# FidoBark11.net
KiCad netlist of a schematic drawn in EAGLE
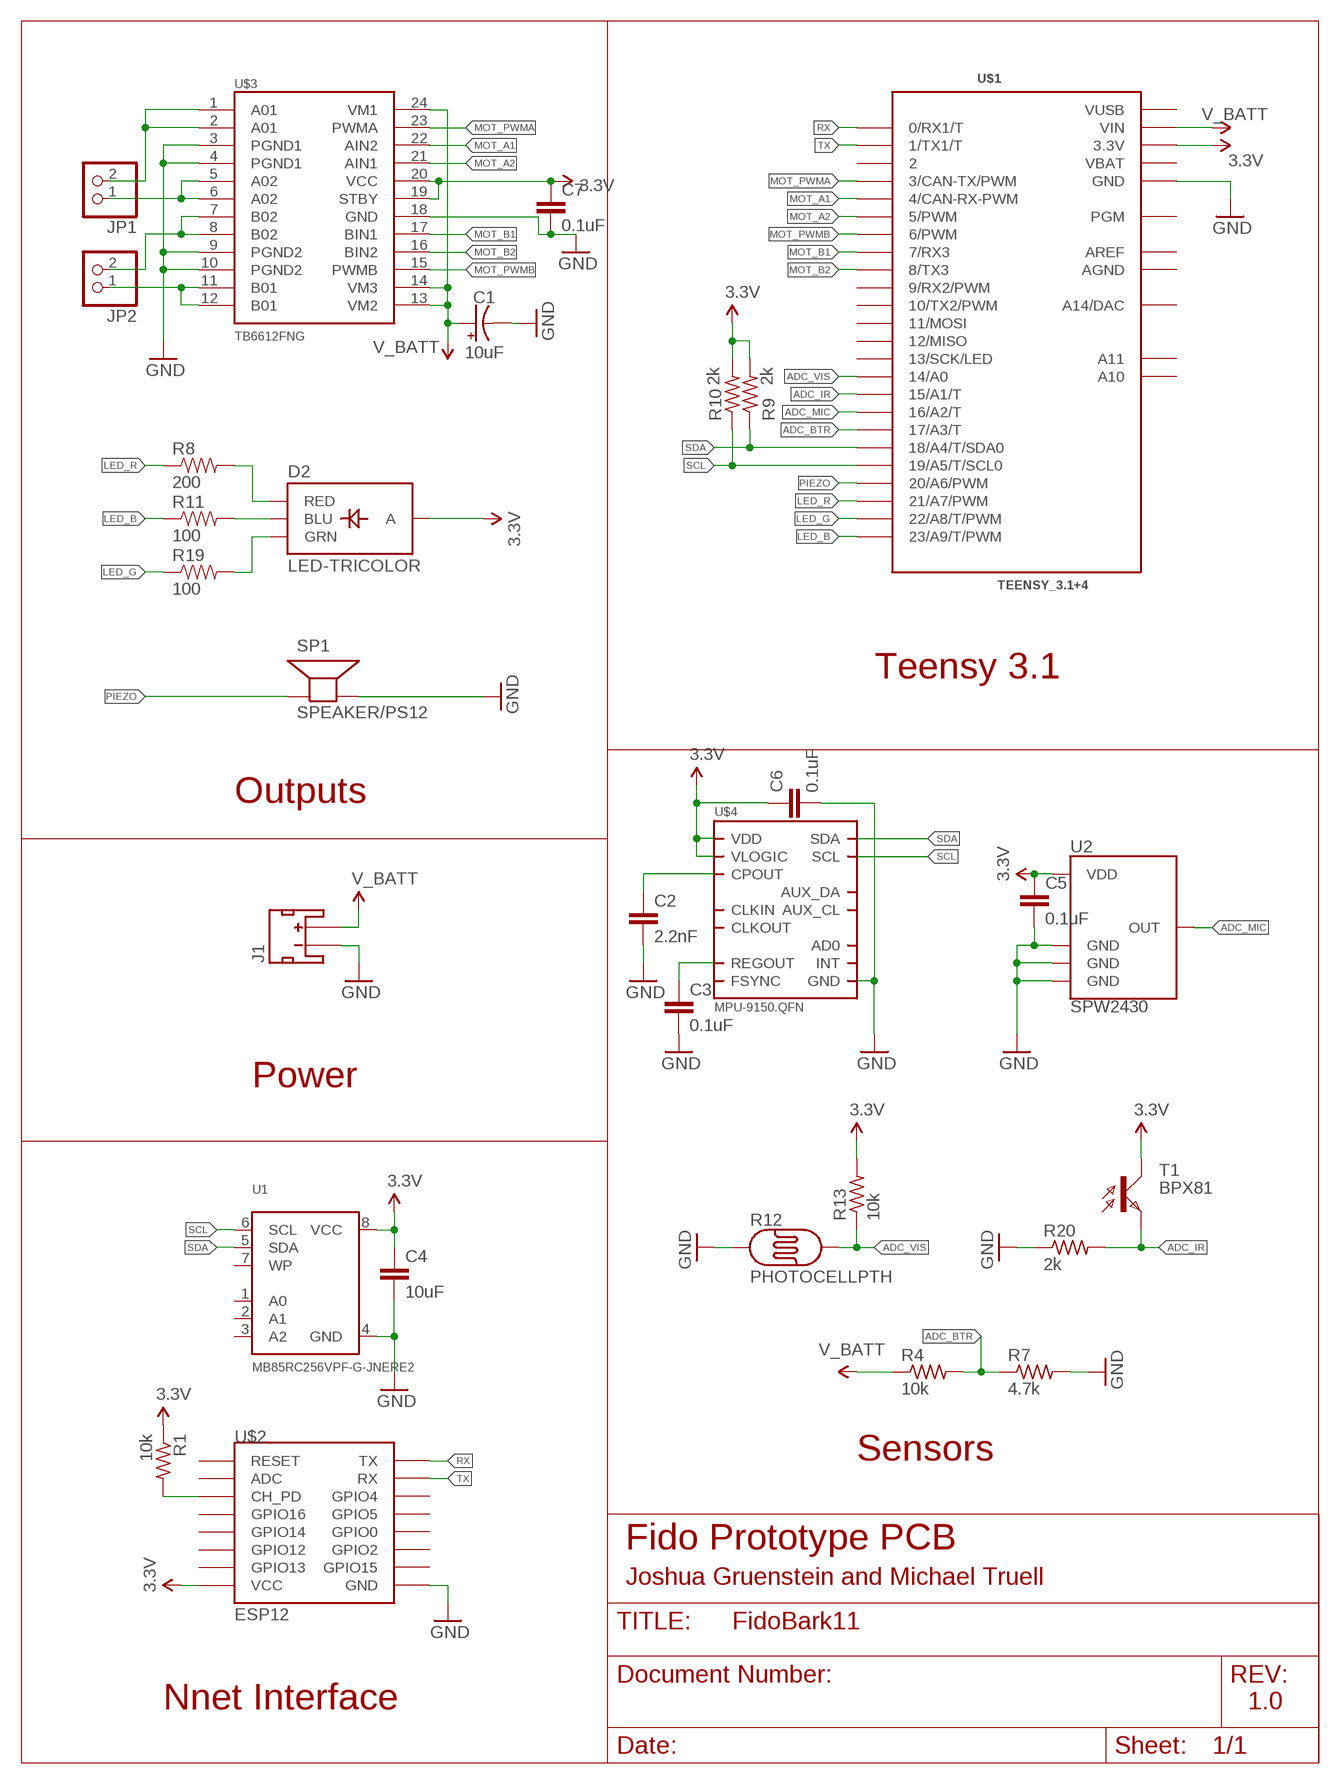
[diagram p0: schematic, sheet 1]

(export (version "E")
  (design (tool "Eeschema 10.0.6"))
  (components
    (comp (ref "C1")
      (value "10uF")
      (footprint "eagle-import:EIA3216")
      (libsource (lib "eagle-import") (part "CAP_POL1206"))
    )
    (comp (ref "C2")
      (value "2.2nF")
      (footprint "eagle-import:C0603")
      (libsource (lib "eagle-import") (part "C-EUC0603"))
    )
    (comp (ref "C3")
      (value "0.1uF")
      (footprint "eagle-import:C0603")
      (libsource (lib "eagle-import") (part "C-EUC0603"))
    )
    (comp (ref "C4")
      (value "10uF")
      (footprint "eagle-import:0603-CAP")
      (libsource (lib "eagle-import") (part "CAP0603-CAP"))
    )
    (comp (ref "C5")
      (value "0.1uF")
      (footprint "eagle-import:C0603")
      (libsource (lib "eagle-import") (part "resistor_C-EUC0603"))
    )
    (comp (ref "C6")
      (value "0.1uF")
      (footprint "eagle-import:C0603")
      (libsource (lib "eagle-import") (part "resistor_C-EUC0603"))
    )
    (comp (ref "C7")
      (value "0.1uF")
      (footprint "eagle-import:C0603")
      (libsource (lib "eagle-import") (part "resistor_C-EUC0603"))
    )
    (comp (ref "D2")
      (value "LED-TRICOLOR")
      (footprint "eagle-import:LED-TRICOLOR-SMD")
      (libsource (lib "eagle-import") (part "LED-TRICOLOR"))
    )
    (comp (ref "J1")
      (value "JST_2MM_MALE")
      (footprint "eagle-import:JST-2-SMD")
      (libsource (lib "eagle-import") (part "JST_2MM_MALE"))
    )
    (comp (ref "JP1")
      (value "PINHD-1X2")
      (footprint "eagle-import:1X02")
      (libsource (lib "eagle-import") (part "PINHD-1X2"))
    )
    (comp (ref "JP2")
      (value "PINHD-1X2")
      (footprint "eagle-import:1X02")
      (libsource (lib "eagle-import") (part "PINHD-1X2"))
    )
    (comp (ref "R1")
      (value "10k")
      (footprint "eagle-import:R0603")
      (libsource (lib "eagle-import") (part "rcl_R-US_R0603"))
    )
    (comp (ref "R4")
      (value "10k")
      (footprint "eagle-import:R0603")
      (libsource (lib "eagle-import") (part "rcl_R-US_R0603"))
    )
    (comp (ref "R7")
      (value "4.7k")
      (footprint "eagle-import:R0603")
      (libsource (lib "eagle-import") (part "rcl_R-US_R0603"))
    )
    (comp (ref "R8")
      (value "200")
      (footprint "eagle-import:0402-RES")
      (libsource (lib "eagle-import") (part "RESISTOR0402-RES"))
    )
    (comp (ref "R9")
      (value "2k")
      (footprint "eagle-import:R0603")
      (libsource (lib "eagle-import") (part "rcl_R-US_R0603"))
    )
    (comp (ref "R10")
      (value "2k")
      (footprint "eagle-import:R0603")
      (libsource (lib "eagle-import") (part "rcl_R-US_R0603"))
    )
    (comp (ref "R11")
      (value "100")
      (footprint "eagle-import:0402-RES")
      (libsource (lib "eagle-import") (part "RESISTOR0402-RES"))
    )
    (comp (ref "R12")
      (value "PHOTOCELLPTH")
      (footprint "eagle-import:PHOTOCELL")
      (libsource (lib "eagle-import") (part "PHOTOCELLPTH"))
    )
    (comp (ref "R13")
      (value "10k")
      (footprint "eagle-import:R0603")
      (libsource (lib "eagle-import") (part "R-US_R0603"))
    )
    (comp (ref "R19")
      (value "100")
      (footprint "eagle-import:0402-RES")
      (libsource (lib "eagle-import") (part "RESISTOR0402-RES"))
    )
    (comp (ref "R20")
      (value "2k")
      (footprint "eagle-import:R0603")
      (libsource (lib "eagle-import") (part "R-US_R0603"))
    )
    (comp (ref "SP1")
      (value "SPEAKER/PS12")
      (footprint "eagle-import:PS12")
      (libsource (lib "eagle-import") (part "SPEAKER/PS12"))
    )
    (comp (ref "T1")
      (value "BPX81")
      (footprint "eagle-import:BPX81")
      (libsource (lib "eagle-import") (part "BPX81"))
    )
    (comp (ref "U$1")
      (value "TEENSY_3.1+4")
      (footprint "eagle-import:TEENSY_3.1+4")
      (libsource (lib "eagle-import") (part "TEENSY_3.1+4"))
    )
    (comp (ref "U$2")
      (value "ESP12")
      (footprint "eagle-import:ESP12")
      (libsource (lib "eagle-import") (part "ESP12"))
    )
    (comp (ref "U$3")
      (value "TB6612FNG")
      (footprint "eagle-import:SSOP24")
      (libsource (lib "eagle-import") (part "TB6612FNG"))
    )
    (comp (ref "U$4")
      (value "MPU-9150.QFN")
      (footprint "eagle-import:QFN.24.4X4")
      (libsource (lib "eagle-import") (part "MPU-9150.QFN"))
    )
    (comp (ref "U1")
      (value "MB85RC256VPF-G-JNERE2")
      (footprint "eagle-import:SOIC8_208MIL")
      (libsource (lib "eagle-import") (part "FRAM_SOIC8_I2C"))
    )
    (comp (ref "U2")
      (value "SPW2430")
      (footprint "eagle-import:ADMP401")
      (libsource (lib "eagle-import") (part "ADMP401"))
    )
  )
  (nets
    (net (code "1") (name "/AGND") (class "Default")
      (node (ref "U$1") (pin "AGND") (pinfunction "AGND_AGND") (pintype "power_in"))
    )
    (net (code "2") (name "/AREF") (class "Default")
      (node (ref "U$1") (pin "AREF") (pinfunction "AREF_AREF") (pintype "power_in"))
    )
    (net (code "3") (name "/VBAT") (class "Default")
      (node (ref "U$1") (pin "VBAT") (pinfunction "VBAT_VBAT") (pintype "power_in"))
    )
    (net (code "4") (name "/VUSB") (class "Default")
      (node (ref "U$1") (pin "VUSB") (pinfunction "VUSB_VUSB") (pintype "power_in"))
    )
    (net (code "5") (name "3.3V") (class "Default")
      (node (ref "C4") (pin "1") (pinfunction "1_1") (pintype "passive"))
      (node (ref "C5") (pin "1") (pinfunction "1_1") (pintype "passive"))
      (node (ref "C6") (pin "1") (pinfunction "1_1") (pintype "passive"))
      (node (ref "C7") (pin "1") (pinfunction "1_1") (pintype "passive"))
      (node (ref "D2") (pin "A") (pinfunction "A_A") (pintype "bidirectional"))
      (node (ref "R1") (pin "1") (pinfunction "1_1") (pintype "passive"))
      (node (ref "R10") (pin "2") (pinfunction "2_2") (pintype "passive"))
      (node (ref "R13") (pin "2") (pinfunction "2_2") (pintype "passive"))
      (node (ref "R9") (pin "2") (pinfunction "2_2") (pintype "passive"))
      (node (ref "T1") (pin "C") (pinfunction "C_C") (pintype "passive"))
      (node (ref "U$1") (pin "3.3V") (pinfunction "3.3V_3.3V") (pintype "power_in"))
      (node (ref "U$1") (pin "3.3V1") (pinfunction "3.3V_3.3V1") (pintype "power_in"))
      (node (ref "U$2") (pin "VCC") (pinfunction "VCC_VCC") (pintype "bidirectional"))
      (node (ref "U$3") (pin "19") (pinfunction "STBY_19") (pintype "bidirectional"))
      (node (ref "U$3") (pin "20") (pinfunction "VCC_20") (pintype "bidirectional"))
      (node (ref "U$4") (pin "13") (pinfunction "VDD_13") (pintype "bidirectional"))
      (node (ref "U$4") (pin "3") (pinfunction "VDD_3") (pintype "bidirectional"))
      (node (ref "U$4") (pin "8") (pinfunction "VLOGIC_8") (pintype "bidirectional"))
      (node (ref "U1") (pin "8") (pinfunction "VCC_8") (pintype "power_in"))
      (node (ref "U2") (pin "5") (pinfunction "VDD_5") (pintype "bidirectional"))
    )
    (net (code "6") (name "ADC_BTR") (class "Default")
      (node (ref "R4") (pin "2") (pinfunction "2_2") (pintype "passive"))
      (node (ref "R7") (pin "1") (pinfunction "1_1") (pintype "passive"))
      (node (ref "U$1") (pin "17/A3") (pinfunction "17/A3/T_17/A3") (pintype "bidirectional"))
    )
    (net (code "7") (name "ADC_IR") (class "Default")
      (node (ref "R20") (pin "2") (pinfunction "2_2") (pintype "passive"))
      (node (ref "T1") (pin "E") (pinfunction "E_E") (pintype "passive"))
      (node (ref "U$1") (pin "15/A1") (pinfunction "15/A1/T_15/A1") (pintype "bidirectional"))
    )
    (net (code "8") (name "ADC_MIC") (class "Default")
      (node (ref "U$1") (pin "16/A2") (pinfunction "16/A2/T_16/A2") (pintype "bidirectional"))
      (node (ref "U2") (pin "1") (pinfunction "OUT_1") (pintype "bidirectional"))
    )
    (net (code "9") (name "ADC_VIS") (class "Default")
      (node (ref "R12") (pin "2") (pinfunction "P$2_2") (pintype "bidirectional"))
      (node (ref "R13") (pin "1") (pinfunction "1_1") (pintype "passive"))
      (node (ref "U$1") (pin "14/A0") (pinfunction "14/A0_14/A0") (pintype "bidirectional"))
    )
    (net (code "10") (name "GND") (class "Default")
      (node (ref "C1") (pin "C") (pinfunction "-_C") (pintype "passive"))
      (node (ref "C2") (pin "2") (pinfunction "2_2") (pintype "passive"))
      (node (ref "C3") (pin "2") (pinfunction "2_2") (pintype "passive"))
      (node (ref "C4") (pin "2") (pinfunction "2_2") (pintype "passive"))
      (node (ref "C5") (pin "2") (pinfunction "2_2") (pintype "passive"))
      (node (ref "C6") (pin "2") (pinfunction "2_2") (pintype "passive"))
      (node (ref "C7") (pin "2") (pinfunction "2_2") (pintype "passive"))
      (node (ref "J1") (pin "1") (pinfunction "-_1") (pintype "bidirectional"))
      (node (ref "R12") (pin "1") (pinfunction "P$1_1") (pintype "bidirectional"))
      (node (ref "R20") (pin "1") (pinfunction "1_1") (pintype "passive"))
      (node (ref "R7") (pin "2") (pinfunction "2_2") (pintype "passive"))
      (node (ref "SP1") (pin "P$2") (pinfunction "-_P$2") (pintype "passive"))
      (node (ref "U$1") (pin "GND") (pinfunction "GND_GND") (pintype "power_in"))
      (node (ref "U$1") (pin "GND1") (pinfunction "GND_GND1") (pintype "power_in"))
      (node (ref "U$2") (pin "GND") (pinfunction "GND_GND") (pintype "bidirectional"))
      (node (ref "U$3") (pin "10") (pinfunction "PGND2_10") (pintype "bidirectional"))
      (node (ref "U$3") (pin "18") (pinfunction "GND_18") (pintype "bidirectional"))
      (node (ref "U$3") (pin "3") (pinfunction "PGND1_3") (pintype "bidirectional"))
      (node (ref "U$3") (pin "4") (pinfunction "PGND1_4") (pintype "bidirectional"))
      (node (ref "U$3") (pin "9") (pinfunction "PGND2_9") (pintype "bidirectional"))
      (node (ref "U$4") (pin "15") (pinfunction "GND_15") (pintype "bidirectional"))
      (node (ref "U$4") (pin "17") (pinfunction "GND_17") (pintype "bidirectional"))
      (node (ref "U$4") (pin "18") (pinfunction "GND_18") (pintype "bidirectional"))
      (node (ref "U1") (pin "4") (pinfunction "GND_4") (pintype "power_in"))
      (node (ref "U2") (pin "2") (pinfunction "GND_2") (pintype "bidirectional"))
      (node (ref "U2") (pin "4") (pinfunction "GND_4") (pintype "bidirectional"))
      (node (ref "U2") (pin "6") (pinfunction "GND_6") (pintype "bidirectional"))
    )
    (net (code "11") (name "LED_B") (class "Default")
      (node (ref "R11") (pin "1") (pinfunction "1_1") (pintype "passive"))
      (node (ref "U$1") (pin "23/A9") (pinfunction "23/A9/T/PWM_23/A9") (pintype "bidirectional"))
    )
    (net (code "12") (name "LED_G") (class "Default")
      (node (ref "R19") (pin "1") (pinfunction "1_1") (pintype "passive"))
      (node (ref "U$1") (pin "22/A8") (pinfunction "22/A8/T/PWM_22/A8") (pintype "bidirectional"))
    )
    (net (code "13") (name "LED_R") (class "Default")
      (node (ref "R8") (pin "1") (pinfunction "1_1") (pintype "passive"))
      (node (ref "U$1") (pin "21/A7") (pinfunction "21/A7/PWM_21/A7") (pintype "bidirectional"))
    )
    (net (code "14") (name "MOT_A1") (class "Default")
      (node (ref "U$1") (pin "4") (pinfunction "4/CAN-RX-PWM_4") (pintype "bidirectional"))
      (node (ref "U$3") (pin "22") (pinfunction "AIN2_22") (pintype "bidirectional"))
    )
    (net (code "15") (name "MOT_A2") (class "Default")
      (node (ref "U$1") (pin "5") (pinfunction "5/PWM_5") (pintype "bidirectional"))
      (node (ref "U$3") (pin "21") (pinfunction "AIN1_21") (pintype "bidirectional"))
    )
    (net (code "16") (name "MOT_B1") (class "Default")
      (node (ref "U$1") (pin "7") (pinfunction "7/RX3_7") (pintype "bidirectional"))
      (node (ref "U$3") (pin "17") (pinfunction "BIN1_17") (pintype "bidirectional"))
    )
    (net (code "17") (name "MOT_B2") (class "Default")
      (node (ref "U$1") (pin "8") (pinfunction "8/TX3_8") (pintype "bidirectional"))
      (node (ref "U$3") (pin "16") (pinfunction "BIN2_16") (pintype "bidirectional"))
    )
    (net (code "18") (name "MOT_PWMA") (class "Default")
      (node (ref "U$1") (pin "3") (pinfunction "3/CAN-TX/PWM_3") (pintype "bidirectional"))
      (node (ref "U$3") (pin "23") (pinfunction "PWMA_23") (pintype "bidirectional"))
    )
    (net (code "19") (name "MOT_PWMB") (class "Default")
      (node (ref "U$1") (pin "6") (pinfunction "6/PWM_6") (pintype "bidirectional"))
      (node (ref "U$3") (pin "15") (pinfunction "PWMB_15") (pintype "bidirectional"))
    )
    (net (code "20") (name "Net-(D2-BLU)") (class "Default")
      (node (ref "D2") (pin "B") (pinfunction "BLU_B") (pintype "bidirectional"))
      (node (ref "R11") (pin "2") (pinfunction "2_2") (pintype "passive"))
    )
    (net (code "21") (name "Net-(D2-GRN)") (class "Default")
      (node (ref "D2") (pin "G") (pinfunction "GRN_G") (pintype "bidirectional"))
      (node (ref "R19") (pin "2") (pinfunction "2_2") (pintype "passive"))
    )
    (net (code "22") (name "Net-(D2-RED)") (class "Default")
      (node (ref "D2") (pin "R") (pinfunction "RED_R") (pintype "bidirectional"))
      (node (ref "R8") (pin "2") (pinfunction "2_2") (pintype "passive"))
    )
    (net (code "23") (name "Net-(JP1-Pad1)") (class "Default")
      (node (ref "JP1") (pin "1") (pinfunction "1_1") (pintype "passive"))
      (node (ref "U$3") (pin "5") (pinfunction "A02_5") (pintype "bidirectional"))
      (node (ref "U$3") (pin "6") (pinfunction "A02_6") (pintype "bidirectional"))
    )
    (net (code "24") (name "Net-(JP1-Pad2)") (class "Default")
      (node (ref "JP1") (pin "2") (pinfunction "2_2") (pintype "passive"))
      (node (ref "U$3") (pin "1") (pinfunction "A01_1") (pintype "bidirectional"))
      (node (ref "U$3") (pin "2") (pinfunction "A01_2") (pintype "bidirectional"))
    )
    (net (code "25") (name "Net-(JP2-Pad1)") (class "Default")
      (node (ref "JP2") (pin "1") (pinfunction "1_1") (pintype "passive"))
      (node (ref "U$3") (pin "11") (pinfunction "B01_11") (pintype "bidirectional"))
      (node (ref "U$3") (pin "12") (pinfunction "B01_12") (pintype "bidirectional"))
    )
    (net (code "26") (name "Net-(JP2-Pad2)") (class "Default")
      (node (ref "JP2") (pin "2") (pinfunction "2_2") (pintype "passive"))
      (node (ref "U$3") (pin "7") (pinfunction "B02_7") (pintype "bidirectional"))
      (node (ref "U$3") (pin "8") (pinfunction "B02_8") (pintype "bidirectional"))
    )
    (net (code "27") (name "Net-(R1-Pad2)") (class "Default")
      (node (ref "R1") (pin "2") (pinfunction "2_2") (pintype "passive"))
      (node (ref "U$2") (pin "CH_PD") (pinfunction "CH_PD_CH_PD") (pintype "bidirectional"))
    )
    (net (code "28") (name "Net-(U$4-CPOUT)") (class "Default")
      (node (ref "C2") (pin "1") (pinfunction "1_1") (pintype "passive"))
      (node (ref "U$4") (pin "20") (pinfunction "CPOUT_20") (pintype "bidirectional"))
    )
    (net (code "29") (name "Net-(U$4-REGOUT)") (class "Default")
      (node (ref "C3") (pin "1") (pinfunction "1_1") (pintype "passive"))
      (node (ref "U$4") (pin "10") (pinfunction "REGOUT_10") (pintype "bidirectional"))
    )
    (net (code "30") (name "PIEZO") (class "Default")
      (node (ref "SP1") (pin "P$1") (pinfunction "+_P$1") (pintype "passive"))
      (node (ref "U$1") (pin "20/A6") (pinfunction "20/A6/PWM_20/A6") (pintype "bidirectional"))
    )
    (net (code "31") (name "RX") (class "Default")
      (node (ref "U$1") (pin "0") (pinfunction "0/RX1/T_0") (pintype "bidirectional"))
      (node (ref "U$2") (pin "TX") (pinfunction "TX_TX") (pintype "bidirectional"))
    )
    (net (code "32") (name "SCL") (class "Default")
      (node (ref "R10") (pin "1") (pinfunction "1_1") (pintype "passive"))
      (node (ref "U$1") (pin "19/A5") (pinfunction "19/A5/T/SCL0_19/A5") (pintype "bidirectional"))
      (node (ref "U$4") (pin "23") (pinfunction "SCL_23") (pintype "bidirectional"))
      (node (ref "U1") (pin "6") (pinfunction "SCL_6") (pintype "input"))
    )
    (net (code "33") (name "SDA") (class "Default")
      (node (ref "R9") (pin "1") (pinfunction "1_1") (pintype "passive"))
      (node (ref "U$1") (pin "18/A4") (pinfunction "18/A4/T/SDA0_18/A4") (pintype "bidirectional"))
      (node (ref "U$4") (pin "24") (pinfunction "SDA_24") (pintype "bidirectional"))
      (node (ref "U1") (pin "5") (pinfunction "SDA_5") (pintype "bidirectional"))
    )
    (net (code "34") (name "TX") (class "Default")
      (node (ref "U$1") (pin "1") (pinfunction "1/TX1/T_1") (pintype "bidirectional"))
      (node (ref "U$2") (pin "RX") (pinfunction "RX_RX") (pintype "bidirectional"))
    )
    (net (code "35") (name "V_BATT") (class "Default")
      (node (ref "C1") (pin "A") (pinfunction "+_A") (pintype "passive"))
      (node (ref "J1") (pin "2") (pinfunction "+_2") (pintype "bidirectional"))
      (node (ref "R4") (pin "1") (pinfunction "1_1") (pintype "passive"))
      (node (ref "U$1") (pin "VIN") (pinfunction "VIN_VIN") (pintype "power_in"))
      (node (ref "U$3") (pin "13") (pinfunction "VM2_13") (pintype "bidirectional"))
      (node (ref "U$3") (pin "14") (pinfunction "VM3_14") (pintype "bidirectional"))
      (node (ref "U$3") (pin "24") (pinfunction "VM1_24") (pintype "bidirectional"))
    )
    (net (code "36") (name "unconnected-(J1-PAD1-PadNC1)") (class "Default")
      (node (ref "J1") (pin "NC1") (pinfunction "PAD1_NC1") (pintype "bidirectional"))
    )
    (net (code "37") (name "unconnected-(J1-PAD2-PadNC2)") (class "Default")
      (node (ref "J1") (pin "NC2") (pinfunction "PAD2_NC2") (pintype "bidirectional"))
    )
    (net (code "38") (name "unconnected-(U$1-9{slash}RX2{slash}PWM-Pad9)") (class "Default")
      (node (ref "U$1") (pin "9") (pinfunction "9/RX2/PWM_9") (pintype "bidirectional"))
    )
    (net (code "39") (name "unconnected-(U$1-10{slash}TX2{slash}PWM-Pad10)") (class "Default")
      (node (ref "U$1") (pin "10") (pinfunction "10/TX2/PWM_10") (pintype "bidirectional"))
    )
    (net (code "40") (name "unconnected-(U$1-11{slash}MOSI-Pad11)") (class "Default")
      (node (ref "U$1") (pin "11") (pinfunction "11/MOSI_11") (pintype "bidirectional"))
    )
    (net (code "41") (name "unconnected-(U$1-12{slash}MISO-Pad12)") (class "Default")
      (node (ref "U$1") (pin "12") (pinfunction "12/MISO_12") (pintype "bidirectional"))
    )
    (net (code "42") (name "unconnected-(U$1-13{slash}SCK{slash}LED-Pad13)") (class "Default")
      (node (ref "U$1") (pin "13") (pinfunction "13/SCK/LED_13") (pintype "bidirectional"))
    )
    (net (code "43") (name "unconnected-(U$1-A14{slash}DAC-PadA14)") (class "Default")
      (node (ref "U$1") (pin "A14") (pinfunction "A14/DAC_A14") (pintype "bidirectional"))
    )
    (net (code "44") (name "unconnected-(U$1-Pad2)") (class "Default")
      (node (ref "U$1") (pin "2") (pinfunction "2_2") (pintype "bidirectional"))
    )
    (net (code "45") (name "unconnected-(U$1-PadA10)") (class "Default")
      (node (ref "U$1") (pin "A10") (pinfunction "A10_A10") (pintype "bidirectional"))
    )
    (net (code "46") (name "unconnected-(U$1-PadA11)") (class "Default")
      (node (ref "U$1") (pin "A11") (pinfunction "A11_A11") (pintype "bidirectional"))
    )
    (net (code "47") (name "unconnected-(U$1-PadPGM)") (class "Default")
      (node (ref "U$1") (pin "PGM") (pinfunction "PGM_PGM") (pintype "bidirectional"))
    )
    (net (code "48") (name "unconnected-(U$2-PadADC)") (class "Default")
      (node (ref "U$2") (pin "ADC") (pinfunction "ADC_ADC") (pintype "bidirectional"))
    )
    (net (code "49") (name "unconnected-(U$2-PadGPIO0)") (class "Default")
      (node (ref "U$2") (pin "GPIO0") (pinfunction "GPIO0_GPIO0") (pintype "bidirectional"))
    )
    (net (code "50") (name "unconnected-(U$2-PadGPIO2)") (class "Default")
      (node (ref "U$2") (pin "GPIO2") (pinfunction "GPIO2_GPIO2") (pintype "bidirectional"))
    )
    (net (code "51") (name "unconnected-(U$2-PadGPIO4)") (class "Default")
      (node (ref "U$2") (pin "GPIO4") (pinfunction "GPIO4_GPIO4") (pintype "bidirectional"))
    )
    (net (code "52") (name "unconnected-(U$2-PadGPIO5)") (class "Default")
      (node (ref "U$2") (pin "GPIO5") (pinfunction "GPIO5_GPIO5") (pintype "bidirectional"))
    )
    (net (code "53") (name "unconnected-(U$2-PadGPIO12)") (class "Default")
      (node (ref "U$2") (pin "GPIO12") (pinfunction "GPIO12_GPIO12") (pintype "bidirectional"))
    )
    (net (code "54") (name "unconnected-(U$2-PadGPIO13)") (class "Default")
      (node (ref "U$2") (pin "GPIO13") (pinfunction "GPIO13_GPIO13") (pintype "bidirectional"))
    )
    (net (code "55") (name "unconnected-(U$2-PadGPIO14)") (class "Default")
      (node (ref "U$2") (pin "GPIO14") (pinfunction "GPIO14_GPIO14") (pintype "bidirectional"))
    )
    (net (code "56") (name "unconnected-(U$2-PadGPIO15)") (class "Default")
      (node (ref "U$2") (pin "GPIO15") (pinfunction "GPIO15_GPIO15") (pintype "bidirectional"))
    )
    (net (code "57") (name "unconnected-(U$2-PadGPIO16)") (class "Default")
      (node (ref "U$2") (pin "GPIO16") (pinfunction "GPIO16_GPIO16") (pintype "bidirectional"))
    )
    (net (code "58") (name "unconnected-(U$2-PadRESET)") (class "Default")
      (node (ref "U$2") (pin "RESET") (pinfunction "RESET_RESET") (pintype "bidirectional"))
    )
    (net (code "59") (name "unconnected-(U$4-AD0-Pad9)") (class "Default")
      (node (ref "U$4") (pin "9") (pinfunction "AD0_9") (pintype "bidirectional"))
    )
    (net (code "60") (name "unconnected-(U$4-AUX_CL-Pad7)") (class "Default")
      (node (ref "U$4") (pin "7") (pinfunction "AUX_CL_7") (pintype "bidirectional"))
    )
    (net (code "61") (name "unconnected-(U$4-AUX_DA-Pad6)") (class "Default")
      (node (ref "U$4") (pin "6") (pinfunction "AUX_DA_6") (pintype "bidirectional"))
    )
    (net (code "62") (name "unconnected-(U$4-CLKIN-Pad1)") (class "Default")
      (node (ref "U$4") (pin "1") (pinfunction "CLKIN_1") (pintype "bidirectional"))
    )
    (net (code "63") (name "unconnected-(U$4-CLKOUT-Pad22)") (class "Default")
      (node (ref "U$4") (pin "22") (pinfunction "CLKOUT_22") (pintype "bidirectional"))
    )
    (net (code "64") (name "unconnected-(U$4-FSYNC-Pad11)") (class "Default")
      (node (ref "U$4") (pin "11") (pinfunction "FSYNC_11") (pintype "bidirectional"))
    )
    (net (code "65") (name "unconnected-(U$4-INT-Pad12)") (class "Default")
      (node (ref "U$4") (pin "12") (pinfunction "INT_12") (pintype "bidirectional"))
    )
    (net (code "66") (name "unconnected-(U1-A0-Pad1)") (class "Default")
      (node (ref "U1") (pin "1") (pinfunction "A0_1") (pintype "input"))
    )
    (net (code "67") (name "unconnected-(U1-A1-Pad2)") (class "Default")
      (node (ref "U1") (pin "2") (pinfunction "A1_2") (pintype "input"))
    )
    (net (code "68") (name "unconnected-(U1-A2-Pad3)") (class "Default")
      (node (ref "U1") (pin "3") (pinfunction "A2_3") (pintype "input"))
    )
    (net (code "69") (name "unconnected-(U1-WP-Pad7)") (class "Default")
      (node (ref "U1") (pin "7") (pinfunction "WP_7") (pintype "input"))
    )
  )
)
